# clogic.net
KiCad netlist of a schematic drawn in EAGLE
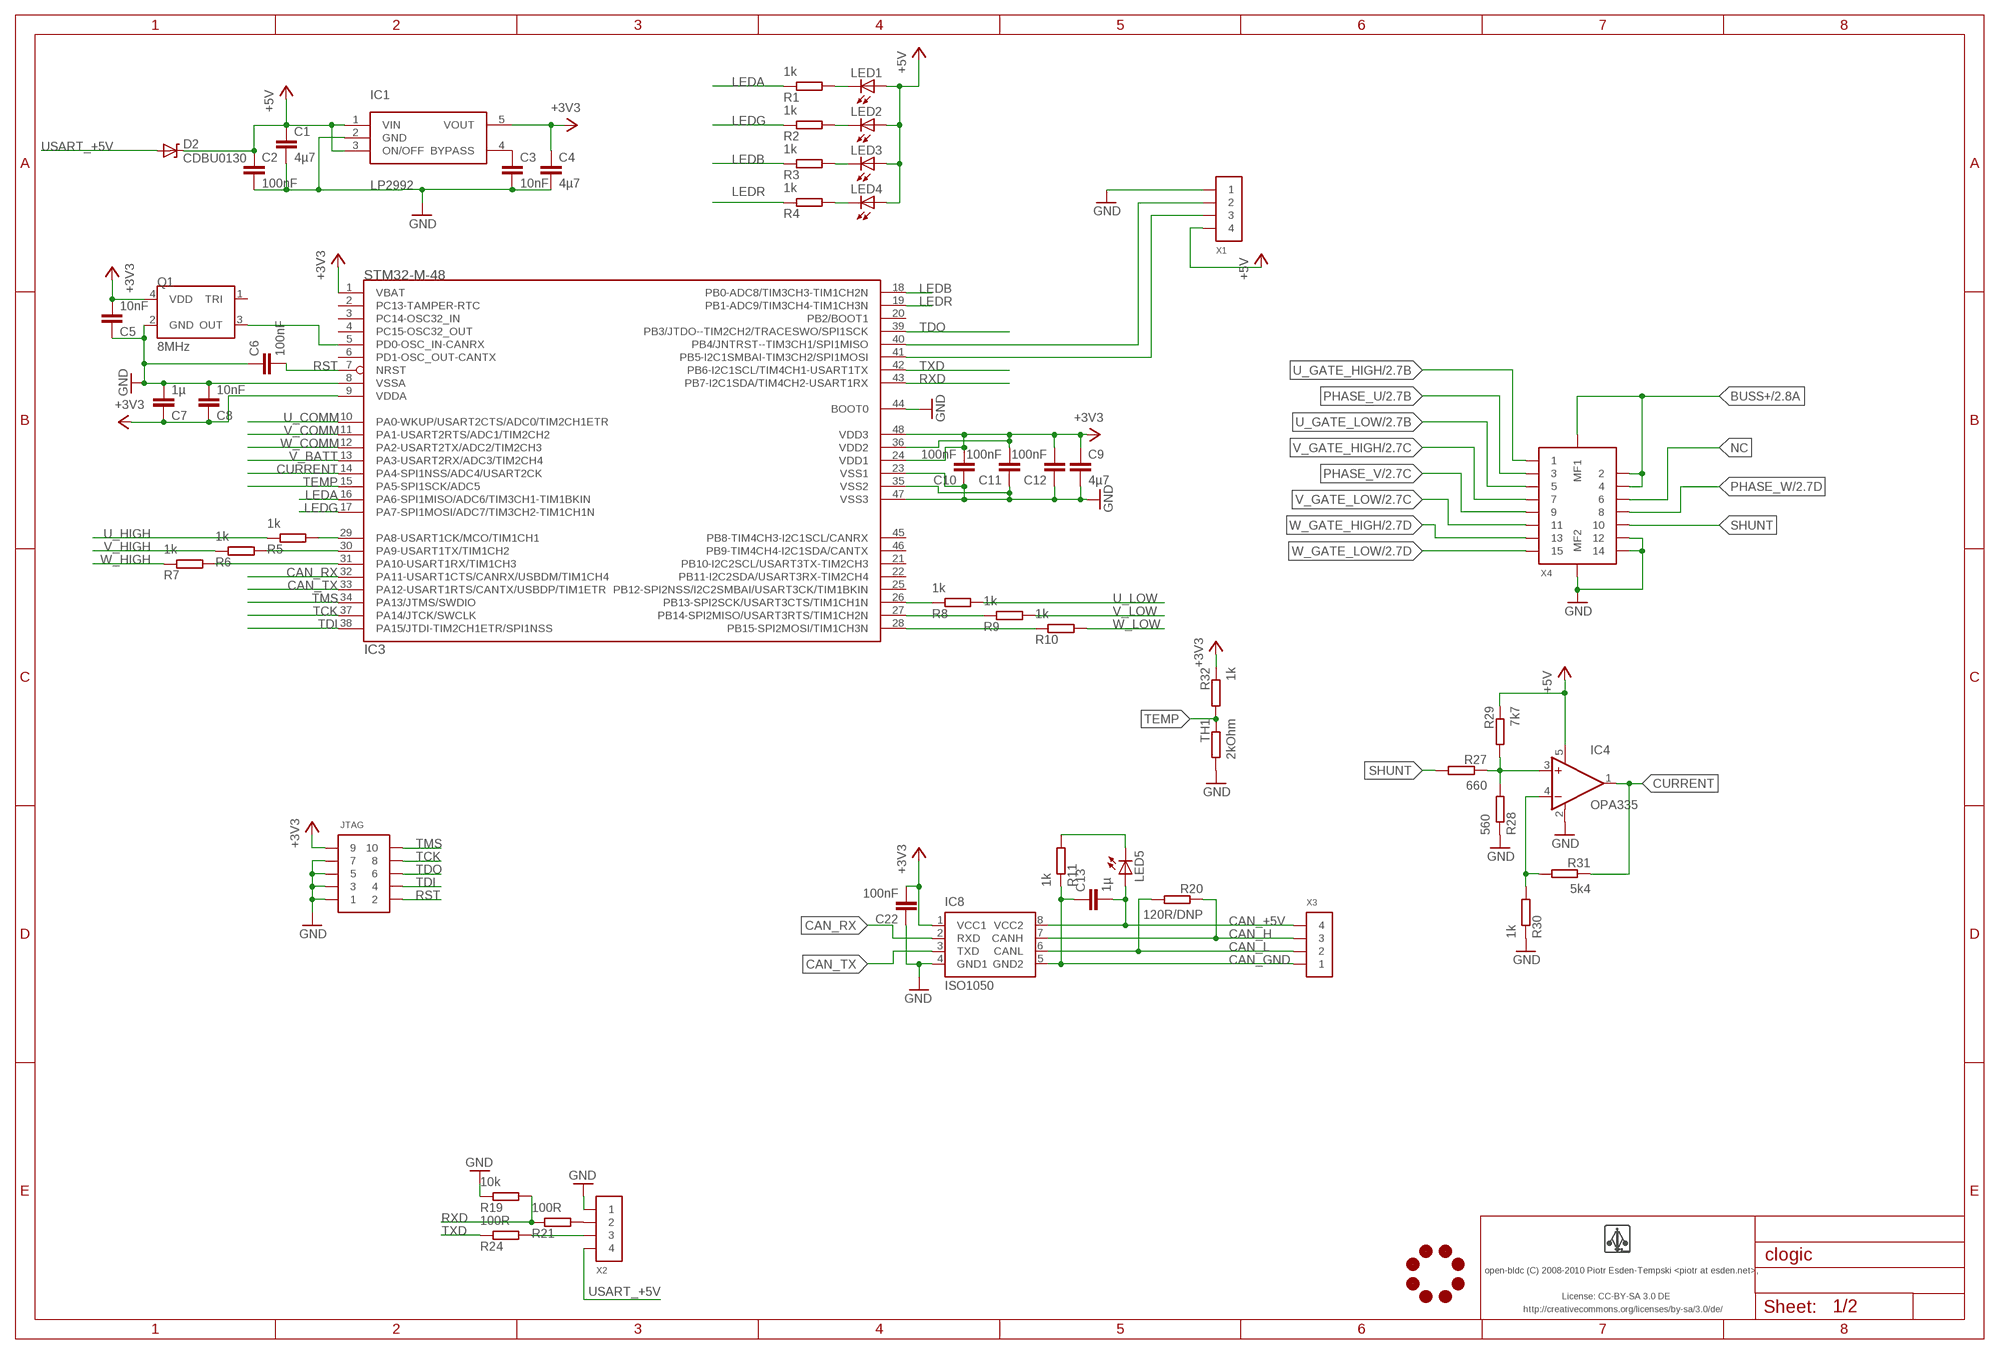
[diagram p0: schematic, sheet 1]
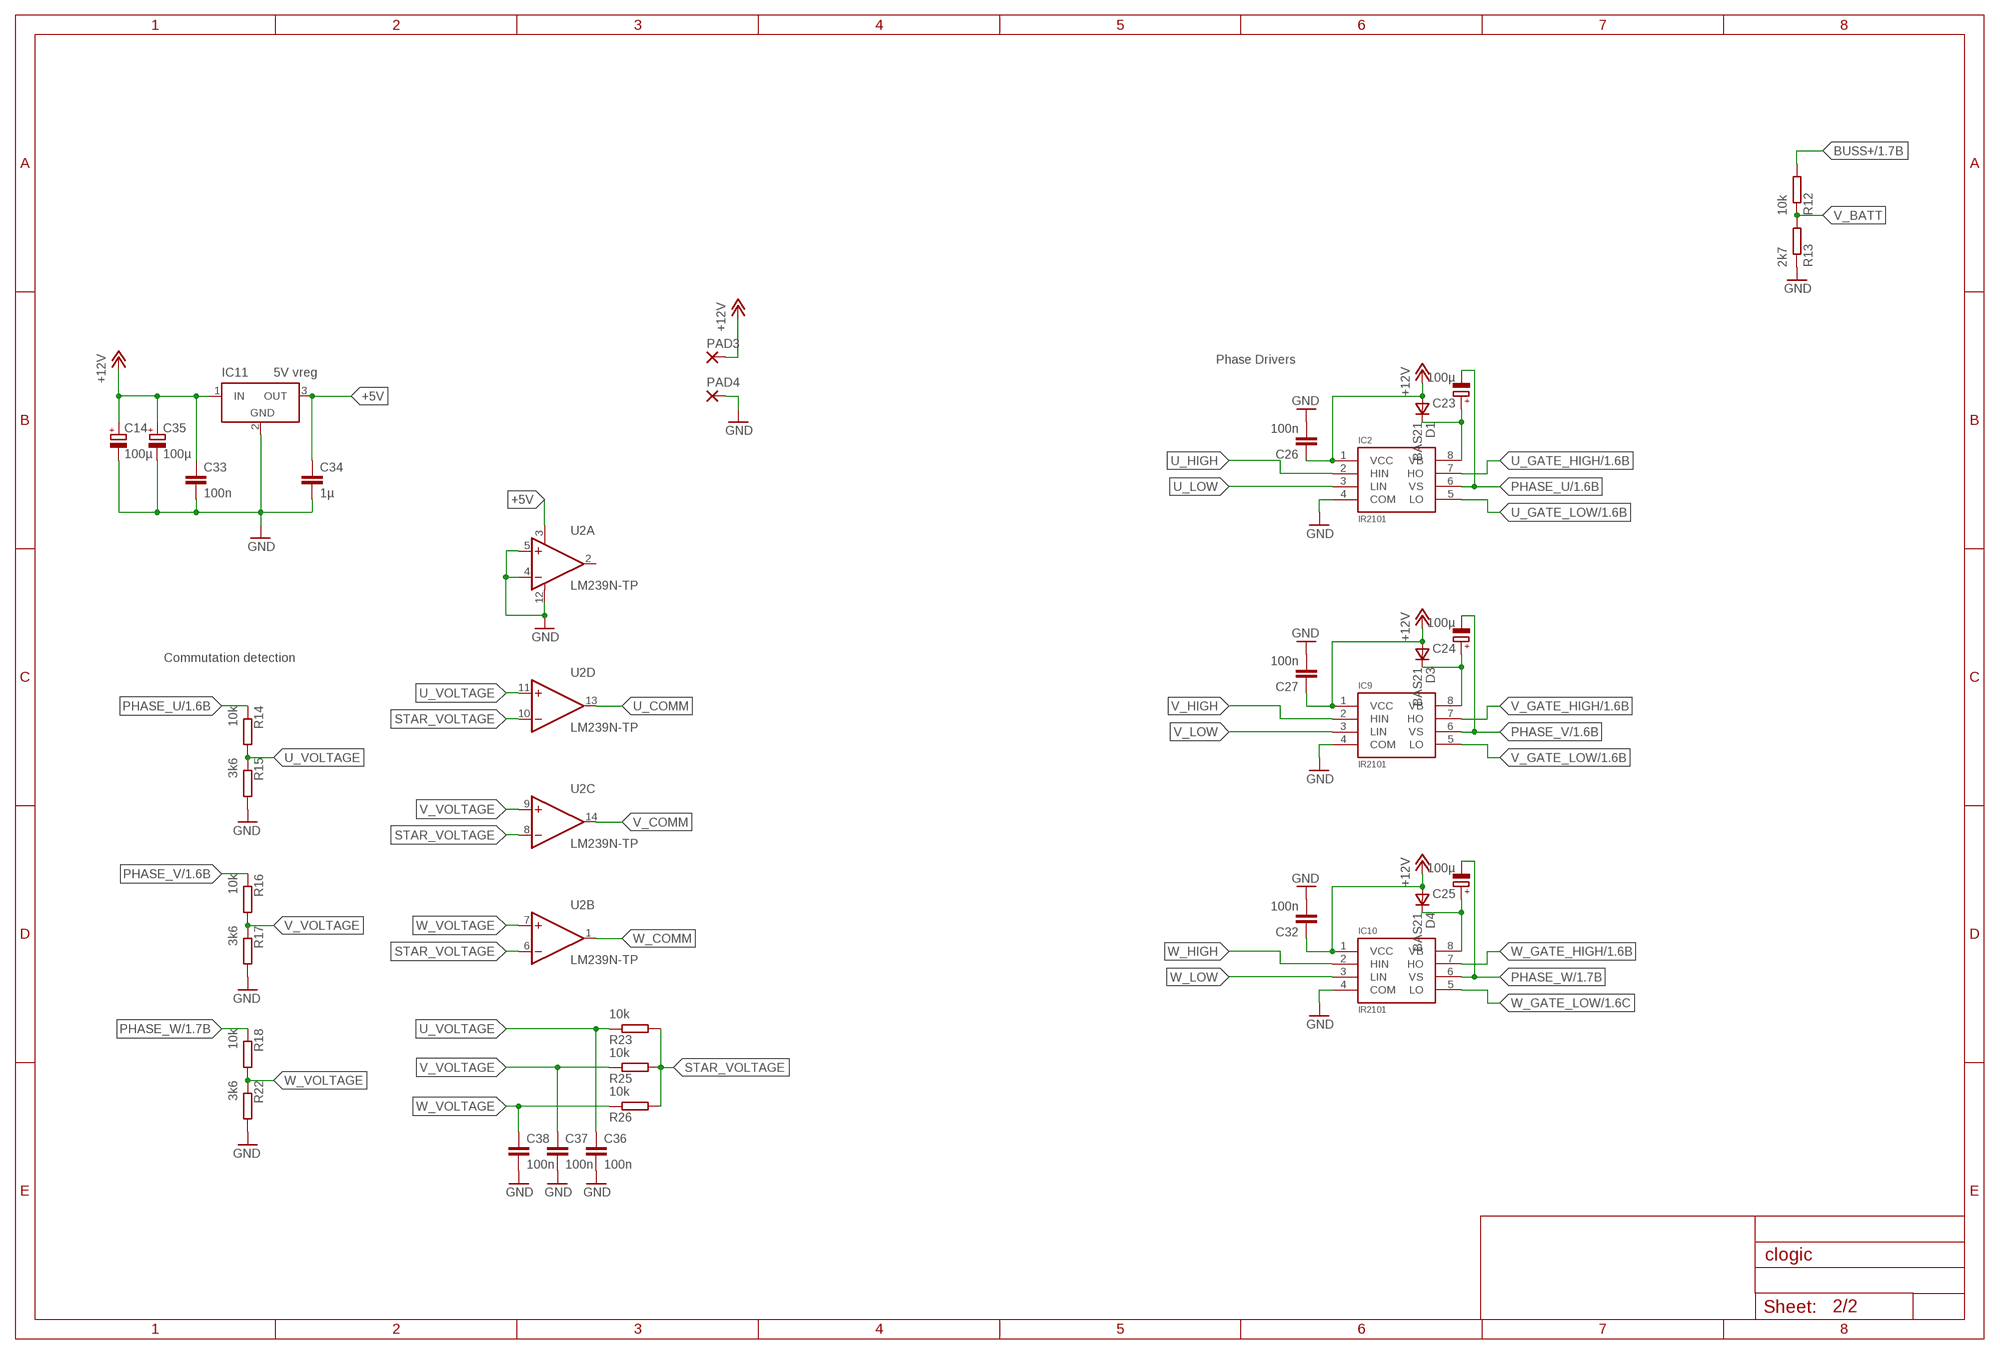
[diagram p1: schematic, sheet 2]

(export (version "E")
  (design (tool "Eeschema 10.0.6"))
  (components
    (comp (ref "C14")
      (value "100µ")
      (footprint "eagle-import:3216_A")
      (libsource (lib "eagle-import") (part "CAPACITOR-POLA"))
    )
    (comp (ref "C23")
      (value "100µ")
      (footprint "eagle-import:0805-POL-CAP")
      (libsource (lib "eagle-import") (part "CAPACITOR-POL-0805"))
    )
    (comp (ref "C24")
      (value "100µ")
      (footprint "eagle-import:0805-POL-CAP")
      (libsource (lib "eagle-import") (part "CAPACITOR-POL-0805"))
    )
    (comp (ref "C25")
      (value "100µ")
      (footprint "eagle-import:0805-POL-CAP")
      (libsource (lib "eagle-import") (part "CAPACITOR-POL-0805"))
    )
    (comp (ref "C26")
      (value "100n")
      (footprint "eagle-import:0603-CAP")
      (libsource (lib "eagle-import") (part "CAPACITOR-0603"))
    )
    (comp (ref "C27")
      (value "100n")
      (footprint "eagle-import:0603-CAP")
      (libsource (lib "eagle-import") (part "CAPACITOR-0603"))
    )
    (comp (ref "C32")
      (value "100n")
      (footprint "eagle-import:0603-CAP")
      (libsource (lib "eagle-import") (part "CAPACITOR-0603"))
    )
    (comp (ref "C33")
      (value "100n")
      (footprint "eagle-import:0603-CAP")
      (libsource (lib "eagle-import") (part "CAPACITOR-0603"))
    )
    (comp (ref "C34")
      (value "1µ")
      (footprint "eagle-import:0603-CAP")
      (libsource (lib "eagle-import") (part "CAPACITOR-0603"))
    )
    (comp (ref "C35")
      (value "100µ")
      (footprint "eagle-import:3216_A")
      (libsource (lib "eagle-import") (part "CAPACITOR-POLA"))
    )
    (comp (ref "C36")
      (value "100n")
      (footprint "eagle-import:0603-CAP")
      (libsource (lib "eagle-import") (part "CAPACITOR-0603"))
    )
    (comp (ref "C37")
      (value "100n")
      (footprint "eagle-import:0603-CAP")
      (libsource (lib "eagle-import") (part "CAPACITOR-0603"))
    )
    (comp (ref "C38")
      (value "100n")
      (footprint "eagle-import:0603-CAP")
      (libsource (lib "eagle-import") (part "CAPACITOR-0603"))
    )
    (comp (ref "D1")
      (value "BAS21")
      (footprint "eagle-import:SOT-23")
      (libsource (lib "eagle-import") (part "VAR2SOT23"))
    )
    (comp (ref "D3")
      (value "BAS21")
      (footprint "eagle-import:SOT-23")
      (libsource (lib "eagle-import") (part "VAR2SOT23"))
    )
    (comp (ref "D4")
      (value "BAS21")
      (footprint "eagle-import:SOT-23")
      (libsource (lib "eagle-import") (part "VAR2SOT23"))
    )
    (comp (ref "IC2")
      (value "IR2101")
      (footprint "eagle-import:SO-8")
      (libsource (lib "eagle-import") (part "IR2101"))
    )
    (comp (ref "IC9")
      (value "IR2101")
      (footprint "eagle-import:SO-8")
      (libsource (lib "eagle-import") (part "IR2101"))
    )
    (comp (ref "IC10")
      (value "IR2101")
      (footprint "eagle-import:SO-8")
      (libsource (lib "eagle-import") (part "IR2101"))
    )
    (comp (ref "IC11")
      (value "5V vreg")
      (footprint "eagle-import:SOT223")
      (libsource (lib "eagle-import") (part "LT1129CST5"))
    )
    (comp (ref "PAD3")
      (value "SMD5")
      (footprint "eagle-import:SMD2,54-5,08")
      (libsource (lib "eagle-import") (part "SMD5"))
    )
    (comp (ref "PAD4")
      (value "SMD5")
      (footprint "eagle-import:SMD2,54-5,08")
      (libsource (lib "eagle-import") (part "SMD5"))
    )
    (comp (ref "R12")
      (value "10k")
      (footprint "eagle-import:0603-RES")
      (libsource (lib "eagle-import") (part "RESISTOR-0603"))
    )
    (comp (ref "R13")
      (value "2k7")
      (footprint "eagle-import:0603-RES")
      (libsource (lib "eagle-import") (part "RESISTOR-0603"))
    )
    (comp (ref "R14")
      (value "10k")
      (footprint "eagle-import:0603-RES")
      (libsource (lib "eagle-import") (part "RESISTOR-0603"))
    )
    (comp (ref "R15")
      (value "3k6")
      (footprint "eagle-import:0603-RES")
      (libsource (lib "eagle-import") (part "RESISTOR-0603"))
    )
    (comp (ref "R16")
      (value "10k")
      (footprint "eagle-import:0603-RES")
      (libsource (lib "eagle-import") (part "RESISTOR-0603"))
    )
    (comp (ref "R17")
      (value "3k6")
      (footprint "eagle-import:0603-RES")
      (libsource (lib "eagle-import") (part "RESISTOR-0603"))
    )
    (comp (ref "R18")
      (value "10k")
      (footprint "eagle-import:0603-RES")
      (libsource (lib "eagle-import") (part "RESISTOR-0603"))
    )
    (comp (ref "R22")
      (value "3k6")
      (footprint "eagle-import:0603-RES")
      (libsource (lib "eagle-import") (part "RESISTOR-0603"))
    )
    (comp (ref "R23")
      (value "10k")
      (footprint "eagle-import:0603-RES")
      (libsource (lib "eagle-import") (part "RESISTOR-0603"))
    )
    (comp (ref "R25")
      (value "10k")
      (footprint "eagle-import:0603-RES")
      (libsource (lib "eagle-import") (part "RESISTOR-0603"))
    )
    (comp (ref "R26")
      (value "10k")
      (footprint "eagle-import:0603-RES")
      (libsource (lib "eagle-import") (part "RESISTOR-0603"))
    )
    (comp (ref "U2")
      (value "LM239N-TP")
      (footprint "eagle-import:TSSOP_14")
      (libsource (lib "eagle-import") (part "LM239N-TP"))
    )
    (comp (ref "C1")
      (value "4µ7")
      (footprint "eagle-import:0603-CAP")
      (libsource (lib "eagle-import") (part "CAPACITOR-0603"))
    )
    (comp (ref "C2")
      (value "100nF")
      (footprint "eagle-import:0603-CAP")
      (libsource (lib "eagle-import") (part "CAPACITOR-0603"))
    )
    (comp (ref "C3")
      (value "10nF")
      (footprint "eagle-import:0603-CAP")
      (libsource (lib "eagle-import") (part "CAPACITOR-0603"))
    )
    (comp (ref "C4")
      (value "4µ7")
      (footprint "eagle-import:0603-CAP")
      (libsource (lib "eagle-import") (part "CAPACITOR-0603"))
    )
    (comp (ref "C5")
      (value "10nF")
      (footprint "eagle-import:0603-CAP")
      (libsource (lib "eagle-import") (part "CAPACITOR-0603"))
    )
    (comp (ref "C6")
      (value "100nF")
      (footprint "eagle-import:0603-CAP")
      (libsource (lib "eagle-import") (part "CAPACITOR-0603"))
    )
    (comp (ref "C7")
      (value "1µ")
      (footprint "eagle-import:0603-CAP")
      (libsource (lib "eagle-import") (part "CAPACITOR-0603"))
    )
    (comp (ref "C8")
      (value "10nF")
      (footprint "eagle-import:0603-CAP")
      (libsource (lib "eagle-import") (part "CAPACITOR-0603"))
    )
    (comp (ref "C9")
      (value "4µ7")
      (footprint "eagle-import:0603-CAP")
      (libsource (lib "eagle-import") (part "CAPACITOR-0603"))
    )
    (comp (ref "C10")
      (value "100nF")
      (footprint "eagle-import:0603-CAP")
      (libsource (lib "eagle-import") (part "CAPACITOR-0603"))
    )
    (comp (ref "C11")
      (value "100nF")
      (footprint "eagle-import:0603-CAP")
      (libsource (lib "eagle-import") (part "CAPACITOR-0603"))
    )
    (comp (ref "C12")
      (value "100nF")
      (footprint "eagle-import:0603-CAP")
      (libsource (lib "eagle-import") (part "CAPACITOR-0603"))
    )
    (comp (ref "C13")
      (value "1µ")
      (footprint "eagle-import:0603-CAP")
      (libsource (lib "eagle-import") (part "CAPACITOR-0603"))
    )
    (comp (ref "C22")
      (value "100nF")
      (footprint "eagle-import:0603-CAP")
      (libsource (lib "eagle-import") (part "CAPACITOR-0603"))
    )
    (comp (ref "D2")
      (value "CDBU0130")
      (footprint "eagle-import:0603-LED")
      (libsource (lib "eagle-import") (part "DIODE-ZENER-0603"))
    )
    (comp (ref "IC1")
      (value "LP2992")
      (footprint "eagle-import:SOT23-5")
      (libsource (lib "eagle-import") (part "LP2992"))
    )
    (comp (ref "IC3")
      (value "STM32-M-48")
      (footprint "eagle-import:LQFP48")
      (libsource (lib "eagle-import") (part "STM32-M-48"))
    )
    (comp (ref "IC4")
      (value "OPA335")
      (footprint "eagle-import:SOT23-5")
      (libsource (lib "eagle-import") (part "OPA335"))
    )
    (comp (ref "IC8")
      (value "ISO1050")
      (footprint "eagle-import:SO8")
      (libsource (lib "eagle-import") (part "ISO1050"))
    )
    (comp (ref "JL1")
      (value "JOBY_LOGO-6MIL")
      (footprint "eagle-import:JOBY_LOGO_6MIL")
      (libsource (lib "eagle-import") (part "JOBY_LOGO-6MIL"))
    )
    (comp (ref "JTAG")
      (value "CONN_5-2-FTSH-V")
      (footprint "eagle-import:FTSH-105-DV")
      (libsource (lib "eagle-import") (part "CONN_5-2-FTSH-V"))
    )
    (comp (ref "LED1")
      (value "AMBER")
      (footprint "eagle-import:0603-LED")
      (libsource (lib "eagle-import") (part "LED-0603"))
    )
    (comp (ref "LED2")
      (value "GREEN")
      (footprint "eagle-import:0603-LED")
      (libsource (lib "eagle-import") (part "LED-0603"))
    )
    (comp (ref "LED3")
      (value "BLUE")
      (footprint "eagle-import:0603-LED")
      (libsource (lib "eagle-import") (part "LED-0603"))
    )
    (comp (ref "LED4")
      (value "RED")
      (footprint "eagle-import:0603-LED")
      (libsource (lib "eagle-import") (part "LED-0603"))
    )
    (comp (ref "LED5")
      (value "WHITE")
      (footprint "eagle-import:0603-LED")
      (libsource (lib "eagle-import") (part "LED-0603"))
    )
    (comp (ref "Q1")
      (value "8MHz")
      (footprint "eagle-import:ASE_OSCILLATOR")
      (libsource (lib "eagle-import") (part "ASE_ASCILLATOR"))
    )
    (comp (ref "R1")
      (value "1k")
      (footprint "eagle-import:0603-RES")
      (libsource (lib "eagle-import") (part "RESISTOR-0603"))
    )
    (comp (ref "R2")
      (value "1k")
      (footprint "eagle-import:0603-RES")
      (libsource (lib "eagle-import") (part "RESISTOR-0603"))
    )
    (comp (ref "R3")
      (value "1k")
      (footprint "eagle-import:0603-RES")
      (libsource (lib "eagle-import") (part "RESISTOR-0603"))
    )
    (comp (ref "R4")
      (value "1k")
      (footprint "eagle-import:0603-RES")
      (libsource (lib "eagle-import") (part "RESISTOR-0603"))
    )
    (comp (ref "R5")
      (value "1k")
      (footprint "eagle-import:0603-RES")
      (libsource (lib "eagle-import") (part "RESISTOR-0603"))
    )
    (comp (ref "R6")
      (value "1k")
      (footprint "eagle-import:0603-RES")
      (libsource (lib "eagle-import") (part "RESISTOR-0603"))
    )
    (comp (ref "R7")
      (value "1k")
      (footprint "eagle-import:0603-RES")
      (libsource (lib "eagle-import") (part "RESISTOR-0603"))
    )
    (comp (ref "R8")
      (value "1k")
      (footprint "eagle-import:0603-RES")
      (libsource (lib "eagle-import") (part "RESISTOR-0603"))
    )
    (comp (ref "R9")
      (value "1k")
      (footprint "eagle-import:0603-RES")
      (libsource (lib "eagle-import") (part "RESISTOR-0603"))
    )
    (comp (ref "R10")
      (value "1k")
      (footprint "eagle-import:0603-RES")
      (libsource (lib "eagle-import") (part "RESISTOR-0603"))
    )
    (comp (ref "R11")
      (value "1k")
      (footprint "eagle-import:0603-RES")
      (libsource (lib "eagle-import") (part "RESISTOR-0603"))
    )
    (comp (ref "R19")
      (value "10k")
      (footprint "eagle-import:0603-RES")
      (libsource (lib "eagle-import") (part "RESISTOR-0603"))
    )
    (comp (ref "R20")
      (value "120R/DNP")
      (footprint "eagle-import:0603-RES")
      (libsource (lib "eagle-import") (part "RESISTOR-0603"))
    )
    (comp (ref "R21")
      (value "100R")
      (footprint "eagle-import:0603-RES")
      (libsource (lib "eagle-import") (part "RESISTOR-0603"))
    )
    (comp (ref "R24")
      (value "100R")
      (footprint "eagle-import:0603-RES")
      (libsource (lib "eagle-import") (part "RESISTOR-0603"))
    )
    (comp (ref "R27")
      (value "660")
      (footprint "eagle-import:0603-RES")
      (libsource (lib "eagle-import") (part "RESISTOR-0603"))
    )
    (comp (ref "R28")
      (value "560")
      (footprint "eagle-import:0603-RES")
      (libsource (lib "eagle-import") (part "RESISTOR-0603"))
    )
    (comp (ref "R29")
      (value "7k7")
      (footprint "eagle-import:0603-RES")
      (libsource (lib "eagle-import") (part "RESISTOR-0603"))
    )
    (comp (ref "R30")
      (value "1k")
      (footprint "eagle-import:0603-RES")
      (libsource (lib "eagle-import") (part "RESISTOR-0603"))
    )
    (comp (ref "R31")
      (value "5k4")
      (footprint "eagle-import:0603-RES")
      (libsource (lib "eagle-import") (part "RESISTOR-0603"))
    )
    (comp (ref "R32")
      (value "1k")
      (footprint "eagle-import:0603-RES")
      (libsource (lib "eagle-import") (part "RESISTOR-0603"))
    )
    (comp (ref "TH1")
      (value "2kOhm")
      (footprint "eagle-import:0603-RES")
      (libsource (lib "eagle-import") (part "RESISTOR-0603"))
    )
    (comp (ref "U$1")
      (value "LOGO")
      (footprint "eagle-import:LOGO")
      (libsource (lib "eagle-import") (part "LOGO-NORM"))
    )
    (comp (ref "X1")
      (value "CONN_4-1-53261")
      (footprint "eagle-import:PB-53261-04")
      (libsource (lib "eagle-import") (part "CONN_4-1-53261"))
    )
    (comp (ref "X2")
      (value "CONN_4-1-53261")
      (footprint "eagle-import:PB-53261-04")
      (libsource (lib "eagle-import") (part "CONN_4-1-53261"))
    )
    (comp (ref "X3")
      (value "CONN_4-1-53261")
      (footprint "eagle-import:PB-53261-04")
      (libsource (lib "eagle-import") (part "CONN_4-1-53261"))
    )
    (comp (ref "X4")
      (value "CONN_15-2-2MT-DF9")
      (footprint "eagle-import:DF9-15")
      (libsource (lib "eagle-import") (part "CONN_15-2-2MT-DF9"))
    )
  )
  (nets
    (net (code "1") (name "+3V3") (class "Default")
      (node (ref "C10") (pin "P$2") (pinfunction "2_P$2") (pintype "passive"))
      (node (ref "C11") (pin "P$2") (pinfunction "2_P$2") (pintype "passive"))
      (node (ref "C12") (pin "P$2") (pinfunction "2_P$2") (pintype "passive"))
      (node (ref "C22") (pin "P$2") (pinfunction "2_P$2") (pintype "passive"))
      (node (ref "C4") (pin "P$1") (pinfunction "1_P$1") (pintype "passive"))
      (node (ref "C5") (pin "P$2") (pinfunction "2_P$2") (pintype "passive"))
      (node (ref "C7") (pin "P$1") (pinfunction "1_P$1") (pintype "passive"))
      (node (ref "C8") (pin "P$1") (pinfunction "1_P$1") (pintype "passive"))
      (node (ref "C9") (pin "P$1") (pinfunction "1_P$1") (pintype "passive"))
      (node (ref "IC1") (pin "5") (pinfunction "VOUT_5") (pintype "bidirectional"))
      (node (ref "IC3") (pin "1") (pinfunction "VBAT_1") (pintype "power_in"))
      (node (ref "IC3") (pin "24") (pinfunction "VDD1_24") (pintype "power_in"))
      (node (ref "IC3") (pin "36") (pinfunction "VDD2_36") (pintype "power_in"))
      (node (ref "IC3") (pin "48") (pinfunction "VDD3_48") (pintype "power_in"))
      (node (ref "IC3") (pin "9") (pinfunction "VDDA_9") (pintype "power_in"))
      (node (ref "IC8") (pin "1") (pinfunction "VCC1_1") (pintype "power_in"))
      (node (ref "JTAG") (pin "9") (pinfunction "9_9") (pintype "bidirectional"))
      (node (ref "Q1") (pin "4") (pinfunction "VDD_4") (pintype "power_in"))
      (node (ref "R32") (pin "P$1") (pinfunction "1_P$1") (pintype "passive"))
    )
    (net (code "2") (name "+5V") (class "Default")
      (node (ref "C1") (pin "P$1") (pinfunction "1_P$1") (pintype "passive"))
      (node (ref "C2") (pin "P$1") (pinfunction "1_P$1") (pintype "passive"))
      (node (ref "C34") (pin "P$1") (pinfunction "1_P$1") (pintype "passive"))
      (node (ref "D2") (pin "C") (pinfunction "C_C") (pintype "passive"))
      (node (ref "IC1") (pin "1") (pinfunction "VIN_1") (pintype "bidirectional"))
      (node (ref "IC1") (pin "3") (pinfunction "ON/OFF_3") (pintype "bidirectional"))
      (node (ref "IC11") (pin "3") (pinfunction "OUT_3") (pintype "power_in"))
      (node (ref "IC4") (pin "5") (pinfunction "V+_5") (pintype "power_in"))
      (node (ref "LED1") (pin "A") (pinfunction "A_A") (pintype "passive"))
      (node (ref "LED2") (pin "A") (pinfunction "A_A") (pintype "passive"))
      (node (ref "LED3") (pin "A") (pinfunction "A_A") (pintype "passive"))
      (node (ref "LED4") (pin "A") (pinfunction "A_A") (pintype "passive"))
      (node (ref "R29") (pin "P$1") (pinfunction "1_P$1") (pintype "passive"))
      (node (ref "U2") (pin "3") (pinfunction "V+_3") (pintype "power_in"))
      (node (ref "X1") (pin "4") (pinfunction "4_4") (pintype "bidirectional"))
    )
    (net (code "3") (name "+12V") (class "Default")
      (node (ref "C14") (pin "+") (pinfunction "+_+") (pintype "passive"))
      (node (ref "C26") (pin "P$1") (pinfunction "1_P$1") (pintype "passive"))
      (node (ref "C27") (pin "P$1") (pinfunction "1_P$1") (pintype "passive"))
      (node (ref "C32") (pin "P$1") (pinfunction "1_P$1") (pintype "passive"))
      (node (ref "C33") (pin "P$1") (pinfunction "1_P$1") (pintype "passive"))
      (node (ref "C35") (pin "+") (pinfunction "+_+") (pintype "passive"))
      (node (ref "D1") (pin "3") (pinfunction "A_3") (pintype "passive"))
      (node (ref "D3") (pin "3") (pinfunction "A_3") (pintype "passive"))
      (node (ref "D4") (pin "3") (pinfunction "A_3") (pintype "passive"))
      (node (ref "IC10") (pin "1") (pinfunction "VCC_1") (pintype "bidirectional"))
      (node (ref "IC11") (pin "1") (pinfunction "IN_1") (pintype "input"))
      (node (ref "IC2") (pin "1") (pinfunction "VCC_1") (pintype "bidirectional"))
      (node (ref "IC9") (pin "1") (pinfunction "VCC_1") (pintype "bidirectional"))
      (node (ref "PAD3") (pin "1") (pinfunction "P_1") (pintype "passive"))
    )
    (net (code "4") (name "BUSS+") (class "Default")
      (node (ref "R12") (pin "P$2") (pinfunction "2_P$2") (pintype "passive"))
      (node (ref "X4") (pin "2") (pinfunction "2_2") (pintype "bidirectional"))
      (node (ref "X4") (pin "4") (pinfunction "4_4") (pintype "bidirectional"))
      (node (ref "X4") (pin "MF1") (pinfunction "MF1_MF1") (pintype "bidirectional"))
    )
    (net (code "5") (name "CAN_+5V") (class "Default")
      (node (ref "C13") (pin "P$2") (pinfunction "2_P$2") (pintype "passive"))
      (node (ref "IC8") (pin "8") (pinfunction "VCC2_8") (pintype "power_in"))
      (node (ref "LED5") (pin "A") (pinfunction "A_A") (pintype "passive"))
      (node (ref "X3") (pin "4") (pinfunction "4_4") (pintype "bidirectional"))
    )
    (net (code "6") (name "CAN_GND") (class "Default")
      (node (ref "C13") (pin "P$1") (pinfunction "1_P$1") (pintype "passive"))
      (node (ref "IC8") (pin "5") (pinfunction "GND2_5") (pintype "power_in"))
      (node (ref "R11") (pin "P$1") (pinfunction "1_P$1") (pintype "passive"))
      (node (ref "X3") (pin "1") (pinfunction "1_1") (pintype "bidirectional"))
    )
    (net (code "7") (name "CAN_H") (class "Default")
      (node (ref "IC8") (pin "7") (pinfunction "CANH_7") (pintype "bidirectional"))
      (node (ref "R20") (pin "P$1") (pinfunction "1_P$1") (pintype "passive"))
      (node (ref "X3") (pin "3") (pinfunction "3_3") (pintype "bidirectional"))
    )
    (net (code "8") (name "CAN_L") (class "Default")
      (node (ref "IC8") (pin "6") (pinfunction "CANL_6") (pintype "bidirectional"))
      (node (ref "R20") (pin "P$2") (pinfunction "2_P$2") (pintype "passive"))
      (node (ref "X3") (pin "2") (pinfunction "2_2") (pintype "bidirectional"))
    )
    (net (code "9") (name "CAN_RX") (class "Default")
      (node (ref "IC3") (pin "32") (pinfunction "PA11-USART1CTS/CANRX/USBDM/TIM1CH4_32") (pintype "bidirectional"))
      (node (ref "IC8") (pin "2") (pinfunction "RXD_2") (pintype "output"))
    )
    (net (code "10") (name "CAN_TX") (class "Default")
      (node (ref "IC3") (pin "33") (pinfunction "PA12-USART1RTS/CANTX/USBDP/TIM1ETR_33") (pintype "bidirectional"))
      (node (ref "IC8") (pin "3") (pinfunction "TXD_3") (pintype "input"))
    )
    (net (code "11") (name "CURRENT") (class "Default")
      (node (ref "IC3") (pin "14") (pinfunction "PA4-SPI1NSS/ADC4/USART2CK_14") (pintype "bidirectional"))
      (node (ref "IC4") (pin "1") (pinfunction "OUT_1") (pintype "output"))
      (node (ref "R31") (pin "P$1") (pinfunction "1_P$1") (pintype "passive"))
    )
    (net (code "12") (name "GND") (class "Default")
      (node (ref "C1") (pin "P$2") (pinfunction "2_P$2") (pintype "passive"))
      (node (ref "C10") (pin "P$1") (pinfunction "1_P$1") (pintype "passive"))
      (node (ref "C11") (pin "P$1") (pinfunction "1_P$1") (pintype "passive"))
      (node (ref "C12") (pin "P$1") (pinfunction "1_P$1") (pintype "passive"))
      (node (ref "C14") (pin "-") (pinfunction "-_-") (pintype "passive"))
      (node (ref "C2") (pin "P$2") (pinfunction "2_P$2") (pintype "passive"))
      (node (ref "C22") (pin "P$1") (pinfunction "1_P$1") (pintype "passive"))
      (node (ref "C26") (pin "P$2") (pinfunction "2_P$2") (pintype "passive"))
      (node (ref "C27") (pin "P$2") (pinfunction "2_P$2") (pintype "passive"))
      (node (ref "C3") (pin "P$2") (pinfunction "2_P$2") (pintype "passive"))
      (node (ref "C32") (pin "P$2") (pinfunction "2_P$2") (pintype "passive"))
      (node (ref "C33") (pin "P$2") (pinfunction "2_P$2") (pintype "passive"))
      (node (ref "C34") (pin "P$2") (pinfunction "2_P$2") (pintype "passive"))
      (node (ref "C35") (pin "-") (pinfunction "-_-") (pintype "passive"))
      (node (ref "C36") (pin "P$2") (pinfunction "2_P$2") (pintype "passive"))
      (node (ref "C37") (pin "P$2") (pinfunction "2_P$2") (pintype "passive"))
      (node (ref "C38") (pin "P$2") (pinfunction "2_P$2") (pintype "passive"))
      (node (ref "C4") (pin "P$2") (pinfunction "2_P$2") (pintype "passive"))
      (node (ref "C5") (pin "P$1") (pinfunction "1_P$1") (pintype "passive"))
      (node (ref "C6") (pin "P$1") (pinfunction "1_P$1") (pintype "passive"))
      (node (ref "C7") (pin "P$2") (pinfunction "2_P$2") (pintype "passive"))
      (node (ref "C8") (pin "P$2") (pinfunction "2_P$2") (pintype "passive"))
      (node (ref "C9") (pin "P$2") (pinfunction "2_P$2") (pintype "passive"))
      (node (ref "IC1") (pin "2") (pinfunction "GND_2") (pintype "bidirectional"))
      (node (ref "IC10") (pin "4") (pinfunction "COM_4") (pintype "bidirectional"))
      (node (ref "IC11") (pin "2") (pinfunction "GND_2") (pintype "power_in"))
      (node (ref "IC2") (pin "4") (pinfunction "COM_4") (pintype "bidirectional"))
      (node (ref "IC3") (pin "23") (pinfunction "VSS1_23") (pintype "power_in"))
      (node (ref "IC3") (pin "35") (pinfunction "VSS2_35") (pintype "power_in"))
      (node (ref "IC3") (pin "44") (pinfunction "BOOT0_44") (pintype "input"))
      (node (ref "IC3") (pin "47") (pinfunction "VSS3_47") (pintype "power_in"))
      (node (ref "IC3") (pin "8") (pinfunction "VSSA_8") (pintype "power_in"))
      (node (ref "IC4") (pin "2") (pinfunction "V-_2") (pintype "power_in"))
      (node (ref "IC8") (pin "4") (pinfunction "GND1_4") (pintype "power_in"))
      (node (ref "IC9") (pin "4") (pinfunction "COM_4") (pintype "bidirectional"))
      (node (ref "JTAG") (pin "1") (pinfunction "1_1") (pintype "bidirectional"))
      (node (ref "JTAG") (pin "3") (pinfunction "3_3") (pintype "bidirectional"))
      (node (ref "JTAG") (pin "5") (pinfunction "5_5") (pintype "bidirectional"))
      (node (ref "JTAG") (pin "7") (pinfunction "7_7") (pintype "bidirectional"))
      (node (ref "PAD4") (pin "1") (pinfunction "P_1") (pintype "passive"))
      (node (ref "Q1") (pin "2") (pinfunction "GND_2") (pintype "power_in"))
      (node (ref "R13") (pin "P$1") (pinfunction "1_P$1") (pintype "passive"))
      (node (ref "R15") (pin "P$2") (pinfunction "2_P$2") (pintype "passive"))
      (node (ref "R17") (pin "P$2") (pinfunction "2_P$2") (pintype "passive"))
      (node (ref "R19") (pin "P$1") (pinfunction "1_P$1") (pintype "passive"))
      (node (ref "R22") (pin "P$2") (pinfunction "2_P$2") (pintype "passive"))
      (node (ref "R28") (pin "P$1") (pinfunction "1_P$1") (pintype "passive"))
      (node (ref "R30") (pin "P$1") (pinfunction "1_P$1") (pintype "passive"))
      (node (ref "TH1") (pin "P$2") (pinfunction "2_P$2") (pintype "passive"))
      (node (ref "U2") (pin "12") (pinfunction "V-_12") (pintype "power_in"))
      (node (ref "U2") (pin "4") (pinfunction "-IN_4") (pintype "input"))
      (node (ref "U2") (pin "5") (pinfunction "+IN_5") (pintype "input"))
      (node (ref "X1") (pin "1") (pinfunction "1_1") (pintype "bidirectional"))
      (node (ref "X2") (pin "1") (pinfunction "1_1") (pintype "bidirectional"))
      (node (ref "X4") (pin "12") (pinfunction "12_12") (pintype "bidirectional"))
      (node (ref "X4") (pin "14") (pinfunction "14_14") (pintype "bidirectional"))
      (node (ref "X4") (pin "MF2") (pinfunction "MF2_MF2") (pintype "bidirectional"))
    )
    (net (code "13") (name "LEDA") (class "Default")
      (node (ref "IC3") (pin "16") (pinfunction "PA6-SPI1MISO/ADC6/TIM3CH1-TIM1BKIN_16") (pintype "bidirectional"))
      (node (ref "R1") (pin "P$1") (pinfunction "1_P$1") (pintype "passive"))
    )
    (net (code "14") (name "LEDB") (class "Default")
      (node (ref "IC3") (pin "18") (pinfunction "PB0-ADC8/TIM3CH3-TIM1CH2N_18") (pintype "bidirectional"))
      (node (ref "R3") (pin "P$1") (pinfunction "1_P$1") (pintype "passive"))
    )
    (net (code "15") (name "LEDG") (class "Default")
      (node (ref "IC3") (pin "17") (pinfunction "PA7-SPI1MOSI/ADC7/TIM3CH2-TIM1CH1N_17") (pintype "bidirectional"))
      (node (ref "R2") (pin "P$1") (pinfunction "1_P$1") (pintype "passive"))
    )
    (net (code "16") (name "LEDR") (class "Default")
      (node (ref "IC3") (pin "19") (pinfunction "PB1-ADC9/TIM3CH4-TIM1CH3N_19") (pintype "bidirectional"))
      (node (ref "R4") (pin "P$1") (pinfunction "1_P$1") (pintype "passive"))
    )
    (net (code "17") (name "NC") (class "Default")
      (node (ref "X4") (pin "6") (pinfunction "6_6") (pintype "bidirectional"))
    )
    (net (code "18") (name "Net-(C3-1)") (class "Default")
      (node (ref "C3") (pin "P$1") (pinfunction "1_P$1") (pintype "passive"))
      (node (ref "IC1") (pin "4") (pinfunction "BYPASS_4") (pintype "bidirectional"))
    )
    (net (code "19") (name "Net-(D1-C)") (class "Default")
      (node (ref "C23") (pin "+") (pinfunction "+_+") (pintype "passive"))
      (node (ref "D1") (pin "1") (pinfunction "C_1") (pintype "passive"))
      (node (ref "IC2") (pin "8") (pinfunction "VB_8") (pintype "bidirectional"))
    )
    (net (code "20") (name "Net-(D3-C)") (class "Default")
      (node (ref "C24") (pin "+") (pinfunction "+_+") (pintype "passive"))
      (node (ref "D3") (pin "1") (pinfunction "C_1") (pintype "passive"))
      (node (ref "IC9") (pin "8") (pinfunction "VB_8") (pintype "bidirectional"))
    )
    (net (code "21") (name "Net-(D4-C)") (class "Default")
      (node (ref "C25") (pin "+") (pinfunction "+_+") (pintype "passive"))
      (node (ref "D4") (pin "1") (pinfunction "C_1") (pintype "passive"))
      (node (ref "IC10") (pin "8") (pinfunction "VB_8") (pintype "bidirectional"))
    )
    (net (code "22") (name "Net-(IC3-PA8-USART1CK{slash}MCO{slash}TIM1CH1)") (class "Default")
      (node (ref "IC3") (pin "29") (pinfunction "PA8-USART1CK/MCO/TIM1CH1_29") (pintype "bidirectional"))
      (node (ref "R5") (pin "P$2") (pinfunction "2_P$2") (pintype "passive"))
    )
    (net (code "23") (name "Net-(IC3-PA9-USART1TX{slash}TIM1CH2)") (class "Default")
      (node (ref "IC3") (pin "30") (pinfunction "PA9-USART1TX/TIM1CH2_30") (pintype "bidirectional"))
      (node (ref "R6") (pin "P$2") (pinfunction "2_P$2") (pintype "passive"))
    )
    (net (code "24") (name "Net-(IC3-PA10-USART1RX{slash}TIM1CH3)") (class "Default")
      (node (ref "IC3") (pin "31") (pinfunction "PA10-USART1RX/TIM1CH3_31") (pintype "bidirectional"))
      (node (ref "R7") (pin "P$2") (pinfunction "2_P$2") (pintype "passive"))
    )
    (net (code "25") (name "Net-(IC3-PB4{slash}JNTRST--TIM3CH1{slash}SPI1MISO)") (class "Default")
      (node (ref "IC3") (pin "40") (pinfunction "PB4/JNTRST--TIM3CH1/SPI1MISO_40") (pintype "bidirectional"))
      (node (ref "X1") (pin "2") (pinfunction "2_2") (pintype "bidirectional"))
    )
    (net (code "26") (name "Net-(IC3-PB5-I2C1SMBAI-TIM3CH2{slash}SPI1MOSI)") (class "Default")
      (node (ref "IC3") (pin "41") (pinfunction "PB5-I2C1SMBAI-TIM3CH2/SPI1MOSI_41") (pintype "bidirectional"))
      (node (ref "X1") (pin "3") (pinfunction "3_3") (pintype "bidirectional"))
    )
    (net (code "27") (name "Net-(IC3-PB13-SPI2SCK{slash}USART3CTS{slash}TIM1CH1N)") (class "Default")
      (node (ref "IC3") (pin "26") (pinfunction "PB13-SPI2SCK/USART3CTS/TIM1CH1N_26") (pintype "bidirectional"))
      (node (ref "R8") (pin "P$1") (pinfunction "1_P$1") (pintype "passive"))
    )
    (net (code "28") (name "Net-(IC3-PB14-SPI2MISO{slash}USART3RTS{slash}TIM1CH2N)") (class "Default")
      (node (ref "IC3") (pin "27") (pinfunction "PB14-SPI2MISO/USART3RTS/TIM1CH2N_27") (pintype "bidirectional"))
      (node (ref "R9") (pin "P$1") (pinfunction "1_P$1") (pintype "passive"))
    )
    (net (code "29") (name "Net-(IC3-PB15-SPI2MOSI{slash}TIM1CH3N)") (class "Default")
      (node (ref "IC3") (pin "28") (pinfunction "PB15-SPI2MOSI/TIM1CH3N_28") (pintype "bidirectional"))
      (node (ref "R10") (pin "P$1") (pinfunction "1_P$1") (pintype "passive"))
    )
    (net (code "30") (name "Net-(IC3-PD0-OSC_IN-CANRX)") (class "Default")
      (node (ref "IC3") (pin "5") (pinfunction "PD0-OSC_IN-CANRX_5") (pintype "input"))
      (node (ref "Q1") (pin "3") (pinfunction "OUT_3") (pintype "output"))
    )
    (net (code "31") (name "Net-(IC4-+IN)") (class "Default")
      (node (ref "IC4") (pin "3") (pinfunction "+IN_3") (pintype "input"))
      (node (ref "R27") (pin "P$1") (pinfunction "1_P$1") (pintype "passive"))
      (node (ref "R28") (pin "P$2") (pinfunction "2_P$2") (pintype "passive"))
      (node (ref "R29") (pin "P$2") (pinfunction "2_P$2") (pintype "passive"))
    )
    (net (code "32") (name "Net-(IC4--IN)") (class "Default")
      (node (ref "IC4") (pin "4") (pinfunction "-IN_4") (pintype "input"))
      (node (ref "R30") (pin "P$2") (pinfunction "2_P$2") (pintype "passive"))
      (node (ref "R31") (pin "P$2") (pinfunction "2_P$2") (pintype "passive"))
    )
    (net (code "33") (name "Net-(R1-2)") (class "Default")
      (node (ref "LED1") (pin "C") (pinfunction "C_C") (pintype "passive"))
      (node (ref "R1") (pin "P$2") (pinfunction "2_P$2") (pintype "passive"))
    )
    (net (code "34") (name "Net-(R2-2)") (class "Default")
      (node (ref "LED2") (pin "C") (pinfunction "C_C") (pintype "passive"))
      (node (ref "R2") (pin "P$2") (pinfunction "2_P$2") (pintype "passive"))
    )
    (net (code "35") (name "Net-(R3-2)") (class "Default")
      (node (ref "LED3") (pin "C") (pinfunction "C_C") (pintype "passive"))
      (node (ref "R3") (pin "P$2") (pinfunction "2_P$2") (pintype "passive"))
    )
    (net (code "36") (name "Net-(R4-2)") (class "Default")
      (node (ref "LED4") (pin "C") (pinfunction "C_C") (pintype "passive"))
      (node (ref "R4") (pin "P$2") (pinfunction "2_P$2") (pintype "passive"))
    )
    (net (code "37") (name "Net-(R11-2)") (class "Default")
      (node (ref "LED5") (pin "C") (pinfunction "C_C") (pintype "passive"))
      (node (ref "R11") (pin "P$2") (pinfunction "2_P$2") (pintype "passive"))
    )
    (net (code "38") (name "Net-(R21-2)") (class "Default")
      (node (ref "R21") (pin "P$2") (pinfunction "2_P$2") (pintype "passive"))
      (node (ref "X2") (pin "2") (pinfunction "2_2") (pintype "bidirectional"))
    )
    (net (code "39") (name "Net-(R24-2)") (class "Default")
      (node (ref "R24") (pin "P$2") (pinfunction "2_P$2") (pintype "passive"))
      (node (ref "X2") (pin "3") (pinfunction "3_3") (pintype "bidirectional"))
    )
    (net (code "40") (name "PHASE_U") (class "Default")
      (node (ref "C23") (pin "-") (pinfunction "-_-") (pintype "passive"))
      (node (ref "IC2") (pin "6") (pinfunction "VS_6") (pintype "bidirectional"))
      (node (ref "R14") (pin "P$1") (pinfunction "1_P$1") (pintype "passive"))
      (node (ref "X4") (pin "3") (pinfunction "3_3") (pintype "bidirectional"))
    )
    (net (code "41") (name "PHASE_V") (class "Default")
      (node (ref "C24") (pin "-") (pinfunction "-_-") (pintype "passive"))
      (node (ref "IC9") (pin "6") (pinfunction "VS_6") (pintype "bidirectional"))
      (node (ref "R16") (pin "P$1") (pinfunction "1_P$1") (pintype "passive"))
      (node (ref "X4") (pin "9") (pinfunction "9_9") (pintype "bidirectional"))
    )
    (net (code "42") (name "PHASE_W") (class "Default")
      (node (ref "C25") (pin "-") (pinfunction "-_-") (pintype "passive"))
      (node (ref "IC10") (pin "6") (pinfunction "VS_6") (pintype "bidirectional"))
      (node (ref "R18") (pin "P$1") (pinfunction "1_P$1") (pintype "passive"))
      (node (ref "X4") (pin "8") (pinfunction "8_8") (pintype "bidirectional"))
    )
    (net (code "43") (name "RST") (class "Default")
      (node (ref "C6") (pin "P$2") (pinfunction "2_P$2") (pintype "passive"))
      (node (ref "IC3") (pin "7") (pinfunction "NRST_7") (pintype "bidirectional"))
      (node (ref "JTAG") (pin "2") (pinfunction "2_2") (pintype "bidirectional"))
    )
    (net (code "44") (name "RXD") (class "Default")
      (node (ref "IC3") (pin "43") (pinfunction "PB7-I2C1SDA/TIM4CH2-USART1RX_43") (pintype "bidirectional"))
      (node (ref "R19") (pin "P$2") (pinfunction "2_P$2") (pintype "passive"))
      (node (ref "R21") (pin "P$1") (pinfunction "1_P$1") (pintype "passive"))
    )
    (net (code "45") (name "SHUNT") (class "Default")
      (node (ref "R27") (pin "P$2") (pinfunction "2_P$2") (pintype "passive"))
      (node (ref "X4") (pin "10") (pinfunction "10_10") (pintype "bidirectional"))
    )
    (net (code "46") (name "STAR_VOLTAGE") (class "Default")
      (node (ref "R23") (pin "P$2") (pinfunction "2_P$2") (pintype "passive"))
      (node (ref "R25") (pin "P$2") (pinfunction "2_P$2") (pintype "passive"))
      (node (ref "R26") (pin "P$2") (pinfunction "2_P$2") (pintype "passive"))
      (node (ref "U2") (pin "10") (pinfunction "-IN_10") (pintype "input"))
      (node (ref "U2") (pin "6") (pinfunction "-IN_6") (pintype "input"))
      (node (ref "U2") (pin "8") (pinfunction "-IN_8") (pintype "input"))
    )
    (net (code "47") (name "TCK") (class "Default")
      (node (ref "IC3") (pin "37") (pinfunction "PA14/JTCK/SWCLK_37") (pintype "bidirectional"))
      (node (ref "JTAG") (pin "8") (pinfunction "8_8") (pintype "bidirectional"))
    )
    (net (code "48") (name "TDI") (class "Default")
      (node (ref "IC3") (pin "38") (pinfunction "PA15/JTDI-TIM2CH1ETR/SPI1NSS_38") (pintype "bidirectional"))
      (node (ref "JTAG") (pin "4") (pinfunction "4_4") (pintype "bidirectional"))
    )
    (net (code "49") (name "TDO") (class "Default")
      (node (ref "IC3") (pin "39") (pinfunction "PB3/JTDO--TIM2CH2/TRACESWO/SPI1SCK_39") (pintype "bidirectional"))
      (node (ref "JTAG") (pin "6") (pinfunction "6_6") (pintype "bidirectional"))
    )
    (net (code "50") (name "TEMP") (class "Default")
      (node (ref "IC3") (pin "15") (pinfunction "PA5-SPI1SCK/ADC5_15") (pintype "bidirectional"))
      (node (ref "R32") (pin "P$2") (pinfunction "2_P$2") (pintype "passive"))
      (node (ref "TH1") (pin "P$1") (pinfunction "1_P$1") (pintype "passive"))
    )
    (net (code "51") (name "TMS") (class "Default")
      (node (ref "IC3") (pin "34") (pinfunction "PA13/JTMS/SWDIO_34") (pintype "bidirectional"))
      (node (ref "JTAG") (pin "10") (pinfunction "10_10") (pintype "bidirectional"))
    )
    (net (code "52") (name "TXD") (class "Default")
      (node (ref "IC3") (pin "42") (pinfunction "PB6-I2C1SCL/TIM4CH1-USART1TX_42") (pintype "bidirectional"))
      (node (ref "R24") (pin "P$1") (pinfunction "1_P$1") (pintype "passive"))
    )
    (net (code "53") (name "USART_+5V") (class "Default")
      (node (ref "D2") (pin "A") (pinfunction "A_A") (pintype "passive"))
      (node (ref "X2") (pin "4") (pinfunction "4_4") (pintype "bidirectional"))
    )
    (net (code "54") (name "U_COMM") (class "Default")
      (node (ref "IC3") (pin "10") (pinfunction "PA0-WKUP/USART2CTS/ADC0/TIM2CH1ETR_10") (pintype "bidirectional"))
      (node (ref "U2") (pin "13") (pinfunction "OUT_13") (pintype "output"))
    )
    (net (code "55") (name "U_GATE_HIGH") (class "Default")
      (node (ref "IC2") (pin "7") (pinfunction "HO_7") (pintype "bidirectional"))
      (node (ref "X4") (pin "1") (pinfunction "1_1") (pintype "bidirectional"))
    )
    (net (code "56") (name "U_GATE_LOW") (class "Default")
      (node (ref "IC2") (pin "5") (pinfunction "LO_5") (pintype "bidirectional"))
      (node (ref "X4") (pin "5") (pinfunction "5_5") (pintype "bidirectional"))
    )
    (net (code "57") (name "U_HIGH") (class "Default")
      (node (ref "IC2") (pin "2") (pinfunction "HIN_2") (pintype "bidirectional"))
      (node (ref "R5") (pin "P$1") (pinfunction "1_P$1") (pintype "passive"))
    )
    (net (code "58") (name "U_LOW") (class "Default")
      (node (ref "IC2") (pin "3") (pinfunction "LIN_3") (pintype "bidirectional"))
      (node (ref "R8") (pin "P$2") (pinfunction "2_P$2") (pintype "passive"))
    )
    (net (code "59") (name "U_VOLTAGE") (class "Default")
      (node (ref "C36") (pin "P$1") (pinfunction "1_P$1") (pintype "passive"))
      (node (ref "R14") (pin "P$2") (pinfunction "2_P$2") (pintype "passive"))
      (node (ref "R15") (pin "P$1") (pinfunction "1_P$1") (pintype "passive"))
      (node (ref "R23") (pin "P$1") (pinfunction "1_P$1") (pintype "passive"))
      (node (ref "U2") (pin "11") (pinfunction "+IN_11") (pintype "input"))
    )
    (net (code "60") (name "V_BATT") (class "Default")
      (node (ref "IC3") (pin "13") (pinfunction "PA3-USART2RX/ADC3/TIM2CH4_13") (pintype "bidirectional"))
      (node (ref "R12") (pin "P$1") (pinfunction "1_P$1") (pintype "passive"))
      (node (ref "R13") (pin "P$2") (pinfunction "2_P$2") (pintype "passive"))
    )
    (net (code "61") (name "V_COMM") (class "Default")
      (node (ref "IC3") (pin "11") (pinfunction "PA1-USART2RTS/ADC1/TIM2CH2_11") (pintype "bidirectional"))
      (node (ref "U2") (pin "14") (pinfunction "OUT_14") (pintype "output"))
    )
    (net (code "62") (name "V_GATE_HIGH") (class "Default")
      (node (ref "IC9") (pin "7") (pinfunction "HO_7") (pintype "bidirectional"))
      (node (ref "X4") (pin "7") (pinfunction "7_7") (pintype "bidirectional"))
    )
    (net (code "63") (name "V_GATE_LOW") (class "Default")
      (node (ref "IC9") (pin "5") (pinfunction "LO_5") (pintype "bidirectional"))
      (node (ref "X4") (pin "11") (pinfunction "11_11") (pintype "bidirectional"))
    )
    (net (code "64") (name "V_HIGH") (class "Default")
      (node (ref "IC9") (pin "2") (pinfunction "HIN_2") (pintype "bidirectional"))
      (node (ref "R6") (pin "P$1") (pinfunction "1_P$1") (pintype "passive"))
    )
    (net (code "65") (name "V_LOW") (class "Default")
      (node (ref "IC9") (pin "3") (pinfunction "LIN_3") (pintype "bidirectional"))
      (node (ref "R9") (pin "P$2") (pinfunction "2_P$2") (pintype "passive"))
    )
    (net (code "66") (name "V_VOLTAGE") (class "Default")
      (node (ref "C37") (pin "P$1") (pinfunction "1_P$1") (pintype "passive"))
      (node (ref "R16") (pin "P$2") (pinfunction "2_P$2") (pintype "passive"))
      (node (ref "R17") (pin "P$1") (pinfunction "1_P$1") (pintype "passive"))
      (node (ref "R25") (pin "P$1") (pinfunction "1_P$1") (pintype "passive"))
      (node (ref "U2") (pin "9") (pinfunction "+IN_9") (pintype "input"))
    )
    (net (code "67") (name "W_COMM") (class "Default")
      (node (ref "IC3") (pin "12") (pinfunction "PA2-USART2TX/ADC2/TIM2CH3_12") (pintype "bidirectional"))
      (node (ref "U2") (pin "1") (pinfunction "OUT_1") (pintype "output"))
    )
    (net (code "68") (name "W_GATE_HIGH") (class "Default")
      (node (ref "IC10") (pin "7") (pinfunction "HO_7") (pintype "bidirectional"))
      (node (ref "X4") (pin "13") (pinfunction "13_13") (pintype "bidirectional"))
    )
    (net (code "69") (name "W_GATE_LOW") (class "Default")
      (node (ref "IC10") (pin "5") (pinfunction "LO_5") (pintype "bidirectional"))
      (node (ref "X4") (pin "15") (pinfunction "15_15") (pintype "bidirectional"))
    )
    (net (code "70") (name "W_HIGH") (class "Default")
      (node (ref "IC10") (pin "2") (pinfunction "HIN_2") (pintype "bidirectional"))
      (node (ref "R7") (pin "P$1") (pinfunction "1_P$1") (pintype "passive"))
    )
    (net (code "71") (name "W_LOW") (class "Default")
      (node (ref "IC10") (pin "3") (pinfunction "LIN_3") (pintype "bidirectional"))
      (node (ref "R10") (pin "P$2") (pinfunction "2_P$2") (pintype "passive"))
    )
    (net (code "72") (name "W_VOLTAGE") (class "Default")
      (node (ref "C38") (pin "P$1") (pinfunction "1_P$1") (pintype "passive"))
      (node (ref "R18") (pin "P$2") (pinfunction "2_P$2") (pintype "passive"))
      (node (ref "R22") (pin "P$1") (pinfunction "1_P$1") (pintype "passive"))
      (node (ref "R26") (pin "P$1") (pinfunction "1_P$1") (pintype "passive"))
      (node (ref "U2") (pin "7") (pinfunction "+IN_7") (pintype "input"))
    )
    (net (code "73") (name "unconnected-(IC3-PB2{slash}BOOT1-Pad20)") (class "Default")
      (node (ref "IC3") (pin "20") (pinfunction "PB2/BOOT1_20") (pintype "bidirectional"))
    )
    (net (code "74") (name "unconnected-(IC3-PB8-TIM4CH3-I2C1SCL{slash}CANRX-Pad45)") (class "Default")
      (node (ref "IC3") (pin "45") (pinfunction "PB8-TIM4CH3-I2C1SCL/CANRX_45") (pintype "bidirectional"))
    )
    (net (code "75") (name "unconnected-(IC3-PB9-TIM4CH4-I2C1SDA{slash}CANTX-Pad46)") (class "Default")
      (node (ref "IC3") (pin "46") (pinfunction "PB9-TIM4CH4-I2C1SDA/CANTX_46") (pintype "bidirectional"))
    )
    (net (code "76") (name "unconnected-(IC3-PB10-I2C2SCL{slash}USART3TX-TIM2CH3-Pad21)") (class "Default")
      (node (ref "IC3") (pin "21") (pinfunction "PB10-I2C2SCL/USART3TX-TIM2CH3_21") (pintype "bidirectional"))
    )
    (net (code "77") (name "unconnected-(IC3-PB11-I2C2SDA{slash}USART3RX-TIM2CH4-Pad22)") (class "Default")
      (node (ref "IC3") (pin "22") (pinfunction "PB11-I2C2SDA/USART3RX-TIM2CH4_22") (pintype "bidirectional"))
    )
    (net (code "78") (name "unconnected-(IC3-PB12-SPI2NSS{slash}I2C2SMBAI{slash}USART3CK{slash}TIM1BKIN-Pad25)") (class "Default")
      (node (ref "IC3") (pin "25") (pinfunction "PB12-SPI2NSS/I2C2SMBAI/USART3CK/TIM1BKIN_25") (pintype "bidirectional"))
    )
    (net (code "79") (name "unconnected-(IC3-PC13-TAMPER-RTC-Pad2)") (class "Default")
      (node (ref "IC3") (pin "2") (pinfunction "PC13-TAMPER-RTC_2") (pintype "bidirectional"))
    )
    (net (code "80") (name "unconnected-(IC3-PC14-OSC32_IN-Pad3)") (class "Default")
      (node (ref "IC3") (pin "3") (pinfunction "PC14-OSC32_IN_3") (pintype "bidirectional"))
    )
    (net (code "81") (name "unconnected-(IC3-PC15-OSC32_OUT-Pad4)") (class "Default")
      (node (ref "IC3") (pin "4") (pinfunction "PC15-OSC32_OUT_4") (pintype "bidirectional"))
    )
    (net (code "82") (name "unconnected-(IC3-PD1-OSC_OUT-CANTX-Pad6)") (class "Default")
      (node (ref "IC3") (pin "6") (pinfunction "PD1-OSC_OUT-CANTX_6") (pintype "output"))
    )
    (net (code "83") (name "unconnected-(Q1-TRI-Pad1)") (class "Default")
      (node (ref "Q1") (pin "1") (pinfunction "TRI_1") (pintype "output"))
    )
    (net (code "84") (name "unconnected-(U2A-OUT-Pad2)") (class "Default")
      (node (ref "U2") (pin "2") (pinfunction "OUT_2") (pintype "output"))
    )
  )
)
